# tricorder-sensor-veml6075-mk-1_0.net
KiCad netlist of a schematic drawn in EAGLE
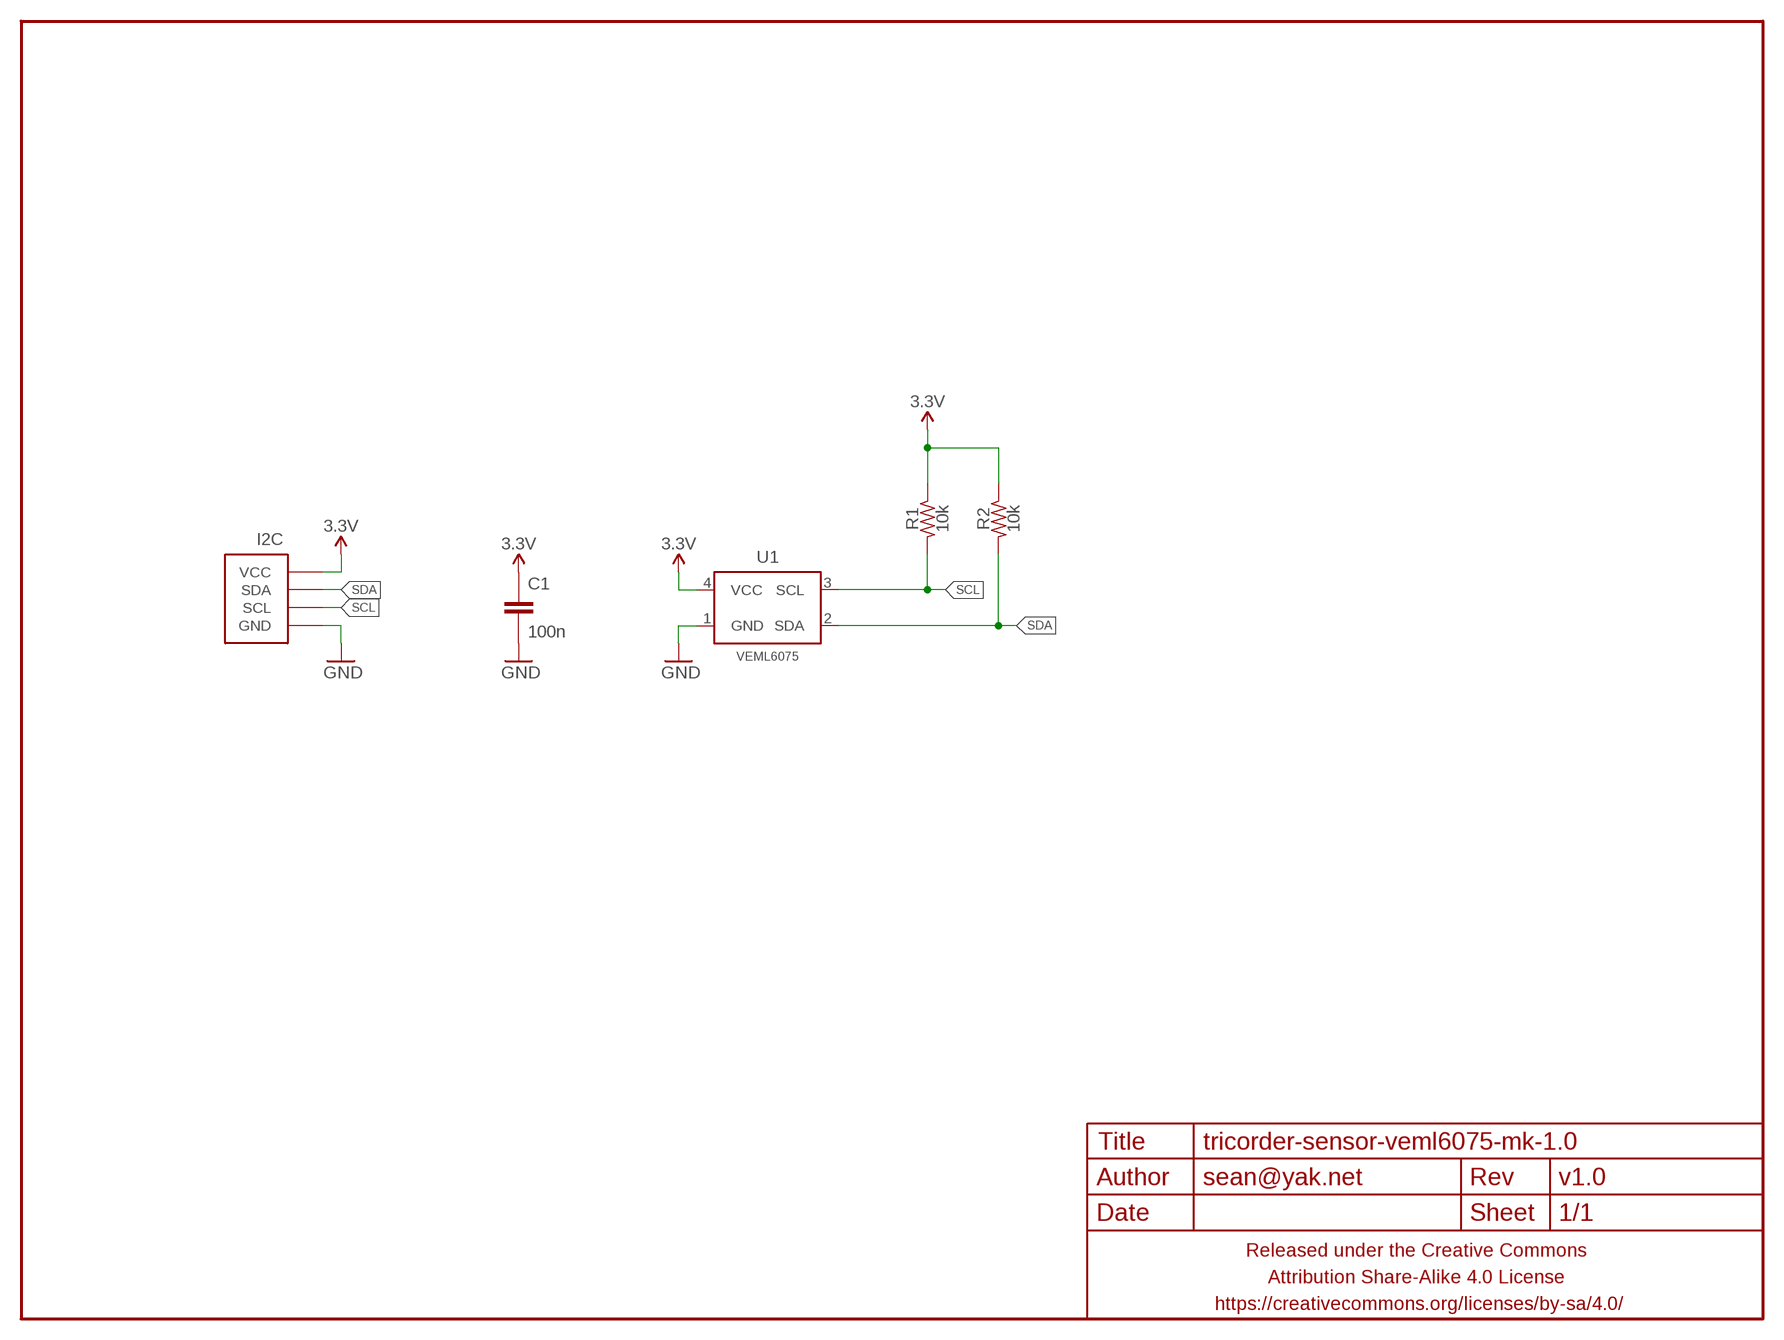
[diagram p0: schematic, sheet 1]

(export (version "E")
  (design (tool "Eeschema 10.0.6"))
  (components
    (comp (ref "C1")
      (value "100n")
      (footprint "eagle-import:C0603")
      (libsource (lib "eagle-import") (part "CAPACITOR-CERAMICC0603"))
    )
    (comp (ref "FRAME1")
      (value "FRAME-LETTERNO_PACKAGE")
      (footprint "eagle-import:DUMMY")
      (fields (field (name "DESIGNER") "sean@yak.net") (field (name "VERSION") "v1.0"))
      (libsource (lib "eagle-import") (part "FRAME-LETTERNO_PACKAGE"))
    )
    (comp (ref "I2C")
      (value "M04-I2CPTH-0.1IN-CENTERED")
      (footprint "eagle-import:1X04-PTH-VERT-I2C-CENTERED")
      (libsource (lib "eagle-import") (part "M04-I2CPTH-0.1IN-CENTERED"))
    )
    (comp (ref "R1")
      (value "10k")
      (footprint "eagle-import:R0603")
      (libsource (lib "eagle-import") (part "RESISTORR0603"))
    )
    (comp (ref "R2")
      (value "10k")
      (footprint "eagle-import:R0603")
      (libsource (lib "eagle-import") (part "RESISTORR0603"))
    )
    (comp (ref "U1")
      (value "VEML6075")
      (footprint "eagle-import:OPLGA4")
      (libsource (lib "eagle-import") (part "VEML6075"))
    )
  )
  (nets
    (net (code "1") (name "3.3V") (class "Default")
      (node (ref "C1") (pin "1") (pinfunction "1_1") (pintype "passive"))
      (node (ref "I2C") (pin "VCC") (pinfunction "VCC_VCC") (pintype "bidirectional"))
      (node (ref "R1") (pin "1") (pinfunction "1_1") (pintype "passive"))
      (node (ref "R2") (pin "1") (pinfunction "1_1") (pintype "passive"))
      (node (ref "U1") (pin "4") (pinfunction "VCC_4") (pintype "bidirectional"))
    )
    (net (code "2") (name "GND") (class "Default")
      (node (ref "C1") (pin "2") (pinfunction "2_2") (pintype "passive"))
      (node (ref "I2C") (pin "GND") (pinfunction "GND_GND") (pintype "bidirectional"))
      (node (ref "U1") (pin "1") (pinfunction "GND_1") (pintype "bidirectional"))
    )
    (net (code "3") (name "SCL") (class "Default")
      (node (ref "I2C") (pin "SCL") (pinfunction "SCL_SCL") (pintype "bidirectional"))
      (node (ref "R1") (pin "2") (pinfunction "2_2") (pintype "passive"))
      (node (ref "U1") (pin "3") (pinfunction "SCL_3") (pintype "bidirectional"))
    )
    (net (code "4") (name "SDA") (class "Default")
      (node (ref "I2C") (pin "SDA") (pinfunction "SDA_SDA") (pintype "bidirectional"))
      (node (ref "R2") (pin "2") (pinfunction "2_2") (pintype "passive"))
      (node (ref "U1") (pin "2") (pinfunction "SDA_2") (pintype "bidirectional"))
    )
  )
)
